# smd.net
KiCad netlist of a schematic drawn in EAGLE
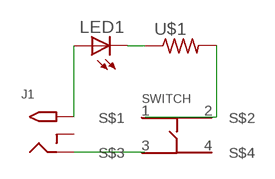
[diagram p0: schematic, sheet 1]

(export (version "E")
  (design (tool "Eeschema 10.0.6"))
  (components
    (comp (ref "J1")
      (value "2.1MMJACKTHM")
      (footprint "eagle-import:PJ-102A")
      (libsource (lib "eagle-import") (part "2.1MMJACKTHM"))
    )
    (comp (ref "LED1")
      (value "LED5MM")
      (footprint "eagle-import:LED5MM")
      (libsource (lib "eagle-import") (part "LED5MM"))
    )
    (comp (ref "S1")
      (value "1301.9315")
      (footprint "eagle-import:1301.9315")
      (libsource (lib "eagle-import") (part "1301.9315"))
    )
    (comp (ref "U$1")
      (value "RESISTORTH-1/4W-CARBON")
      (footprint "eagle-import:RESAD1160W55L680D260_HS")
      (libsource (lib "eagle-import") (part "RESISTORTH-1/4W-CARBON"))
    )
  )
  (nets
    (net (code "1") (name "Net-(J1-PadTIP)") (class "Default")
      (node (ref "J1") (pin "TIP") (pinfunction "TIP_TIP") (pintype "bidirectional"))
      (node (ref "LED1") (pin "A") (pinfunction "A_A") (pintype "passive"))
    )
    (net (code "2") (name "Net-(LED1-C)") (class "Default")
      (node (ref "LED1") (pin "K") (pinfunction "C_K") (pintype "passive"))
      (node (ref "U$1") (pin "1") (pinfunction "1_1") (pintype "passive"))
    )
    (net (code "3") (name "unconnected-(J1-PadRING)") (class "Default")
      (node (ref "J1") (pin "RING") (pinfunction "RING_RING") (pintype "bidirectional"))
    )
    (net (code "4") (name "unconnected-(J1-PadRING_SW)") (class "Default")
      (node (ref "J1") (pin "RING_SW") (pinfunction "RING_SW_RING_SW") (pintype "bidirectional"))
    )
    (net (code "5") (name "unconnected-(S1-S$1-Pad1)") (class "Default")
      (node (ref "S1") (pin "1") (pinfunction "S$1_1") (pintype "bidirectional"))
    )
    (net (code "6") (name "unconnected-(S1-S$2-Pad2)") (class "Default")
      (node (ref "S1") (pin "2") (pinfunction "S$2_2") (pintype "bidirectional"))
    )
    (net (code "7") (name "unconnected-(S1-S$3-Pad3)") (class "Default")
      (node (ref "S1") (pin "3") (pinfunction "S$3_3") (pintype "bidirectional"))
    )
    (net (code "8") (name "unconnected-(S1-S$4-Pad4)") (class "Default")
      (node (ref "S1") (pin "4") (pinfunction "S$4_4") (pintype "bidirectional"))
    )
    (net (code "9") (name "unconnected-(U$1-Pad2)") (class "Default")
      (node (ref "U$1") (pin "2") (pinfunction "2_2") (pintype "passive"))
    )
  )
)
